# Sample_and_Hold_Main.net
KiCad netlist of a schematic drawn in EAGLE
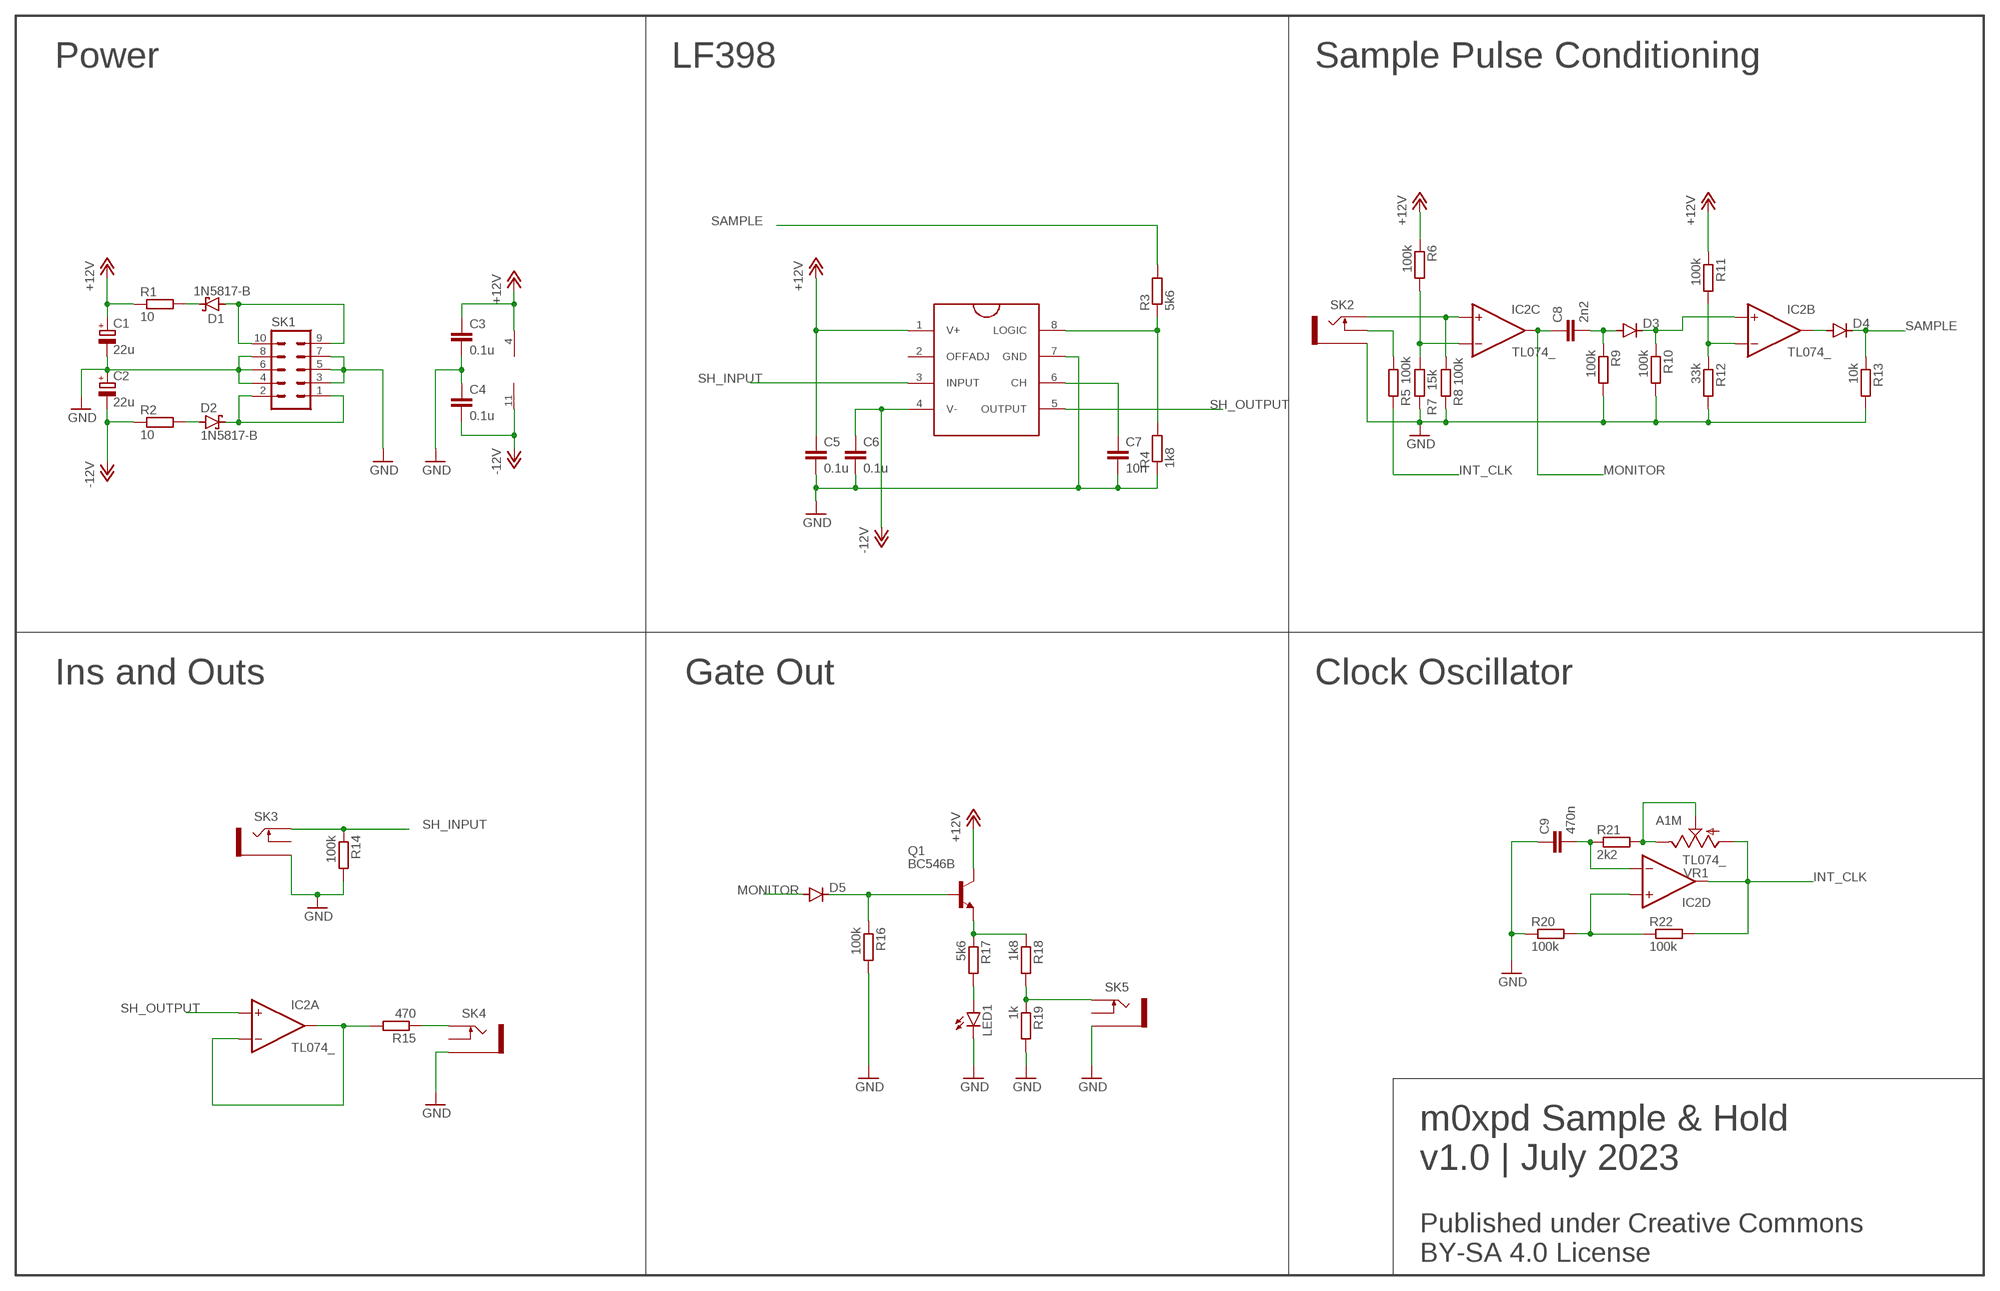
[diagram p0: schematic, sheet 1]

(export (version "E")
  (design (tool "Eeschema 10.0.6"))
  (components
    (comp (ref "C1")
      (value "22u")
      (footprint "eagle-import:E2,5-6")
      (libsource (lib "eagle-import") (part "CPOL-EUE2.5-6"))
    )
    (comp (ref "C2")
      (value "22u")
      (footprint "eagle-import:E2,5-6")
      (libsource (lib "eagle-import") (part "CPOL-EUE2.5-6"))
    )
    (comp (ref "C3")
      (value "0.1u")
      (footprint "eagle-import:C050-024X044")
      (libsource (lib "eagle-import") (part "C-EU050-024X044"))
    )
    (comp (ref "C4")
      (value "0.1u")
      (footprint "eagle-import:C050-024X044")
      (libsource (lib "eagle-import") (part "C-EU050-024X044"))
    )
    (comp (ref "C5")
      (value "0.1u")
      (footprint "eagle-import:C050-024X044")
      (libsource (lib "eagle-import") (part "C-EU050-024X044"))
    )
    (comp (ref "C6")
      (value "0.1u")
      (footprint "eagle-import:C050-024X044")
      (libsource (lib "eagle-import") (part "C-EU050-024X044"))
    )
    (comp (ref "C7")
      (value "10n")
      (footprint "eagle-import:C050-025X075")
      (libsource (lib "eagle-import") (part "C-EU050-025X075"))
    )
    (comp (ref "C8")
      (value "2n2")
      (footprint "eagle-import:C050-024X044")
      (libsource (lib "eagle-import") (part "C-EU050-024X044"))
    )
    (comp (ref "C9")
      (value "470n")
      (footprint "eagle-import:C050-035X075")
      (libsource (lib "eagle-import") (part "C-EU050-035X075"))
    )
    (comp (ref "D1")
      (value "1N5817-B")
      (footprint "eagle-import:DO41-7.6")
      (libsource (lib "eagle-import") (part "1N5817-B"))
    )
    (comp (ref "D2")
      (value "1N5817-B")
      (footprint "eagle-import:DO41-7.6")
      (libsource (lib "eagle-import") (part "1N5817-B"))
    )
    (comp (ref "D3")
      (value "1N4148DO35-7")
      (footprint "eagle-import:DO35-7")
      (libsource (lib "eagle-import") (part "1N4148DO35-7"))
    )
    (comp (ref "D4")
      (value "1N4148DO35-7")
      (footprint "eagle-import:DO35-7")
      (libsource (lib "eagle-import") (part "1N4148DO35-7"))
    )
    (comp (ref "D5")
      (value "1N4148DO35-7")
      (footprint "eagle-import:DO35-7")
      (libsource (lib "eagle-import") (part "1N4148DO35-7"))
    )
    (comp (ref "IC1")
      (value "LF398")
      (footprint "eagle-import:DIL08")
      (libsource (lib "eagle-import") (part "LF398"))
    )
    (comp (ref "IC2")
      (value "TL074_")
      (footprint "eagle-import:DIL14")
      (libsource (lib "eagle-import") (part "TL074_"))
    )
    (comp (ref "LED1")
      (value "LED3MM")
      (footprint "eagle-import:LED3MM")
      (libsource (lib "eagle-import") (part "LED3MM"))
    )
    (comp (ref "Q1")
      (value "BC546B")
      (footprint "eagle-import:TO92-EBC")
      (libsource (lib "eagle-import") (part "BC546B"))
    )
    (comp (ref "R1")
      (value "10")
      (footprint "eagle-import:0204_7")
      (libsource (lib "eagle-import") (part "R-EU_0204/7"))
    )
    (comp (ref "R2")
      (value "10")
      (footprint "eagle-import:0204_7")
      (libsource (lib "eagle-import") (part "R-EU_0204/7"))
    )
    (comp (ref "R3")
      (value "5k6")
      (footprint "eagle-import:0204_7")
      (libsource (lib "eagle-import") (part "R-EU_0204/7"))
    )
    (comp (ref "R4")
      (value "1k8")
      (footprint "eagle-import:0204_7")
      (libsource (lib "eagle-import") (part "R-EU_0204/7"))
    )
    (comp (ref "R5")
      (value "100k")
      (footprint "eagle-import:0204_7")
      (libsource (lib "eagle-import") (part "R-EU_0204/7"))
    )
    (comp (ref "R6")
      (value "100k")
      (footprint "eagle-import:0204_7")
      (libsource (lib "eagle-import") (part "R-EU_0204/7"))
    )
    (comp (ref "R7")
      (value "15k")
      (footprint "eagle-import:0204_7")
      (libsource (lib "eagle-import") (part "R-EU_0204/7"))
    )
    (comp (ref "R8")
      (value "100k")
      (footprint "eagle-import:0204_7")
      (libsource (lib "eagle-import") (part "R-EU_0204/7"))
    )
    (comp (ref "R9")
      (value "100k")
      (footprint "eagle-import:0204_7")
      (libsource (lib "eagle-import") (part "R-EU_0204/7"))
    )
    (comp (ref "R10")
      (value "100k")
      (footprint "eagle-import:0204_7")
      (libsource (lib "eagle-import") (part "R-EU_0204/7"))
    )
    (comp (ref "R11")
      (value "100k")
      (footprint "eagle-import:0204_7")
      (libsource (lib "eagle-import") (part "R-EU_0204/7"))
    )
    (comp (ref "R12")
      (value "33k")
      (footprint "eagle-import:0204_7")
      (libsource (lib "eagle-import") (part "R-EU_0204/7"))
    )
    (comp (ref "R13")
      (value "10k")
      (footprint "eagle-import:0204_7")
      (libsource (lib "eagle-import") (part "R-EU_0204/7"))
    )
    (comp (ref "R14")
      (value "100k")
      (footprint "eagle-import:0204_7")
      (libsource (lib "eagle-import") (part "R-EU_0204/7"))
    )
    (comp (ref "R15")
      (value "470")
      (footprint "eagle-import:0204_7")
      (libsource (lib "eagle-import") (part "R-EU_0204/7"))
    )
    (comp (ref "R16")
      (value "100k")
      (footprint "eagle-import:0204_7")
      (libsource (lib "eagle-import") (part "R-EU_0204/7"))
    )
    (comp (ref "R17")
      (value "5k6")
      (footprint "eagle-import:0204_7")
      (libsource (lib "eagle-import") (part "R-EU_0204/7"))
    )
    (comp (ref "R18")
      (value "1k8")
      (footprint "eagle-import:0204_7")
      (libsource (lib "eagle-import") (part "R-EU_0204/7"))
    )
    (comp (ref "R19")
      (value "1k")
      (footprint "eagle-import:0204_7")
      (libsource (lib "eagle-import") (part "R-EU_0204/7"))
    )
    (comp (ref "R20")
      (value "100k")
      (footprint "eagle-import:0204_7")
      (libsource (lib "eagle-import") (part "R-EU_0204/7"))
    )
    (comp (ref "R21")
      (value "2k2")
      (footprint "eagle-import:0204_7")
      (libsource (lib "eagle-import") (part "R-EU_0204/7"))
    )
    (comp (ref "R22")
      (value "100k")
      (footprint "eagle-import:0204_7")
      (libsource (lib "eagle-import") (part "R-EU_0204/7"))
    )
    (comp (ref "SK1")
      (value "EURO_POWER_HEADERFAT_PADS")
      (footprint "eagle-import:EURO_PWR_HEADER_FAT")
      (libsource (lib "eagle-import") (part "EURO_POWER_HEADERFAT_PADS"))
    )
    (comp (ref "SK2")
      (value "THONKICONNNEW")
      (footprint "eagle-import:WQP-PJ301M-12_JACK")
      (libsource (lib "eagle-import") (part "THONKICONNNEW"))
    )
    (comp (ref "SK3")
      (value "THONKICONNNEW")
      (footprint "eagle-import:WQP-PJ301M-12_JACK")
      (libsource (lib "eagle-import") (part "THONKICONNNEW"))
    )
    (comp (ref "SK4")
      (value "THONKICONNNEW")
      (footprint "eagle-import:WQP-PJ301M-12_JACK")
      (libsource (lib "eagle-import") (part "THONKICONNNEW"))
    )
    (comp (ref "SK5")
      (value "THONKICONNNEW")
      (footprint "eagle-import:WQP-PJ301M-12_JACK")
      (libsource (lib "eagle-import") (part "THONKICONNNEW"))
    )
    (comp (ref "VR1")
      (value "A1M")
      (footprint "eagle-import:9MM_SNAP-IN_POT")
      (libsource (lib "eagle-import") (part "9MM_SNAP-IN_POT_"))
    )
  )
  (nets
    (net (code "1") (name "+12V") (class "Default")
      (node (ref "C1") (pin "+") (pinfunction "+_+") (pintype "passive"))
      (node (ref "C3") (pin "1") (pinfunction "1_1") (pintype "passive"))
      (node (ref "C5") (pin "1") (pinfunction "1_1") (pintype "passive"))
      (node (ref "IC1") (pin "1") (pinfunction "V+_1") (pintype "power_in"))
      (node (ref "IC2") (pin "4") (pinfunction "V+_4") (pintype "power_in"))
      (node (ref "Q1") (pin "C") (pinfunction "C_C") (pintype "passive"))
      (node (ref "R1") (pin "1") (pinfunction "1_1") (pintype "passive"))
      (node (ref "R11") (pin "1") (pinfunction "1_1") (pintype "passive"))
      (node (ref "R6") (pin "1") (pinfunction "1_1") (pintype "passive"))
    )
    (net (code "2") (name "-12V") (class "Default")
      (node (ref "C2") (pin "-") (pinfunction "-_-") (pintype "passive"))
      (node (ref "C4") (pin "2") (pinfunction "2_2") (pintype "passive"))
      (node (ref "C6") (pin "1") (pinfunction "1_1") (pintype "passive"))
      (node (ref "IC1") (pin "4") (pinfunction "V-_4") (pintype "power_in"))
      (node (ref "IC2") (pin "11") (pinfunction "V-_11") (pintype "power_in"))
      (node (ref "R2") (pin "1") (pinfunction "1_1") (pintype "passive"))
    )
    (net (code "3") (name "/INT_CLK") (class "Default")
      (node (ref "IC2") (pin "14") (pinfunction "OUT_14") (pintype "output"))
      (node (ref "R22") (pin "2") (pinfunction "2_2") (pintype "passive"))
      (node (ref "R5") (pin "2") (pinfunction "2_2") (pintype "passive"))
      (node (ref "VR1") (pin "1") (pinfunction "A_1") (pintype "passive"))
    )
    (net (code "4") (name "/MONITOR") (class "Default")
      (node (ref "C8") (pin "1") (pinfunction "1_1") (pintype "passive"))
      (node (ref "D5") (pin "A") (pinfunction "A_A") (pintype "passive"))
      (node (ref "IC2") (pin "8") (pinfunction "OUT_8") (pintype "output"))
    )
    (net (code "5") (name "/SAMPLE") (class "Default")
      (node (ref "D4") (pin "C") (pinfunction "C_C") (pintype "passive"))
      (node (ref "R13") (pin "1") (pinfunction "1_1") (pintype "passive"))
      (node (ref "R3") (pin "2") (pinfunction "2_2") (pintype "passive"))
    )
    (net (code "6") (name "/SH_INPUT") (class "Default")
      (node (ref "IC1") (pin "3") (pinfunction "INPUT_3") (pintype "bidirectional"))
      (node (ref "R14") (pin "1") (pinfunction "1_1") (pintype "passive"))
      (node (ref "SK3") (pin "P$1_TIP") (pinfunction "TIP_P$1_TIP") (pintype "passive"))
    )
    (net (code "7") (name "/SH_OUTPUT") (class "Default")
      (node (ref "IC1") (pin "5") (pinfunction "OUTPUT_5") (pintype "bidirectional"))
      (node (ref "IC2") (pin "3") (pinfunction "+IN_3") (pintype "input"))
    )
    (net (code "8") (name "GND") (class "Default")
      (node (ref "C1") (pin "-") (pinfunction "-_-") (pintype "passive"))
      (node (ref "C2") (pin "+") (pinfunction "+_+") (pintype "passive"))
      (node (ref "C3") (pin "2") (pinfunction "2_2") (pintype "passive"))
      (node (ref "C4") (pin "1") (pinfunction "1_1") (pintype "passive"))
      (node (ref "C5") (pin "2") (pinfunction "2_2") (pintype "passive"))
      (node (ref "C6") (pin "2") (pinfunction "2_2") (pintype "passive"))
      (node (ref "C7") (pin "2") (pinfunction "2_2") (pintype "passive"))
      (node (ref "C9") (pin "1") (pinfunction "1_1") (pintype "passive"))
      (node (ref "IC1") (pin "7") (pinfunction "GND_7") (pintype "power_in"))
      (node (ref "LED1") (pin "K") (pinfunction "C_K") (pintype "passive"))
      (node (ref "R10") (pin "2") (pinfunction "2_2") (pintype "passive"))
      (node (ref "R12") (pin "2") (pinfunction "2_2") (pintype "passive"))
      (node (ref "R13") (pin "2") (pinfunction "2_2") (pintype "passive"))
      (node (ref "R14") (pin "2") (pinfunction "2_2") (pintype "passive"))
      (node (ref "R16") (pin "2") (pinfunction "2_2") (pintype "passive"))
      (node (ref "R19") (pin "2") (pinfunction "2_2") (pintype "passive"))
      (node (ref "R20") (pin "1") (pinfunction "1_1") (pintype "passive"))
      (node (ref "R4") (pin "1") (pinfunction "1_1") (pintype "passive"))
      (node (ref "R7") (pin "2") (pinfunction "2_2") (pintype "passive"))
      (node (ref "R8") (pin "2") (pinfunction "2_2") (pintype "passive"))
      (node (ref "R9") (pin "2") (pinfunction "2_2") (pintype "passive"))
      (node (ref "SK1") (pin "3") (pinfunction "3_3") (pintype "passive"))
      (node (ref "SK1") (pin "4") (pinfunction "4_4") (pintype "passive"))
      (node (ref "SK1") (pin "5") (pinfunction "5_5") (pintype "passive"))
      (node (ref "SK1") (pin "6") (pinfunction "6_6") (pintype "passive"))
      (node (ref "SK1") (pin "7") (pinfunction "7_7") (pintype "passive"))
      (node (ref "SK1") (pin "8") (pinfunction "8_8") (pintype "passive"))
      (node (ref "SK2") (pin "P$3_SLEEVE") (pinfunction "SLEEVE_P$3_SLEEVE") (pintype "passive"))
      (node (ref "SK3") (pin "P$3_SLEEVE") (pinfunction "SLEEVE_P$3_SLEEVE") (pintype "passive"))
      (node (ref "SK4") (pin "P$3_SLEEVE") (pinfunction "SLEEVE_P$3_SLEEVE") (pintype "passive"))
      (node (ref "SK5") (pin "P$3_SLEEVE") (pinfunction "SLEEVE_P$3_SLEEVE") (pintype "passive"))
    )
    (net (code "9") (name "Net-(C8-Pad2)") (class "Default")
      (node (ref "C8") (pin "2") (pinfunction "2_2") (pintype "passive"))
      (node (ref "D3") (pin "A") (pinfunction "A_A") (pintype "passive"))
      (node (ref "R9") (pin "1") (pinfunction "1_1") (pintype "passive"))
    )
    (net (code "10") (name "Net-(D1-PadA)") (class "Default")
      (node (ref "D1") (pin "A") (pinfunction "A_A") (pintype "passive"))
      (node (ref "SK1") (pin "10") (pinfunction "10_10") (pintype "passive"))
      (node (ref "SK1") (pin "9") (pinfunction "9_9") (pintype "passive"))
    )
    (net (code "11") (name "Net-(D1-PadC)") (class "Default")
      (node (ref "D1") (pin "C") (pinfunction "C_C") (pintype "passive"))
      (node (ref "R1") (pin "2") (pinfunction "2_2") (pintype "passive"))
    )
    (net (code "12") (name "Net-(D2-PadA)") (class "Default")
      (node (ref "D2") (pin "A") (pinfunction "A_A") (pintype "passive"))
      (node (ref "R2") (pin "2") (pinfunction "2_2") (pintype "passive"))
    )
    (net (code "13") (name "Net-(D2-PadC)") (class "Default")
      (node (ref "D2") (pin "C") (pinfunction "C_C") (pintype "passive"))
      (node (ref "SK1") (pin "1") (pinfunction "1_1") (pintype "passive"))
      (node (ref "SK1") (pin "2") (pinfunction "2_2") (pintype "passive"))
    )
    (net (code "14") (name "Net-(D5-PadC)") (class "Default")
      (node (ref "D5") (pin "C") (pinfunction "C_C") (pintype "passive"))
      (node (ref "Q1") (pin "B") (pinfunction "B_B") (pintype "passive"))
      (node (ref "R16") (pin "1") (pinfunction "1_1") (pintype "passive"))
    )
    (net (code "15") (name "Net-(IC1-CH)") (class "Default")
      (node (ref "C7") (pin "1") (pinfunction "1_1") (pintype "passive"))
      (node (ref "IC1") (pin "6") (pinfunction "CH_6") (pintype "bidirectional"))
    )
    (net (code "16") (name "Net-(IC1-LOGIC)") (class "Default")
      (node (ref "IC1") (pin "8") (pinfunction "LOGIC_8") (pintype "bidirectional"))
      (node (ref "R3") (pin "1") (pinfunction "1_1") (pintype "passive"))
      (node (ref "R4") (pin "2") (pinfunction "2_2") (pintype "passive"))
    )
    (net (code "17") (name "Net-(IC2A--IN)") (class "Default")
      (node (ref "IC2") (pin "1") (pinfunction "OUT_1") (pintype "output"))
      (node (ref "IC2") (pin "2") (pinfunction "-IN_2") (pintype "input"))
      (node (ref "R15") (pin "2") (pinfunction "2_2") (pintype "passive"))
    )
    (net (code "18") (name "Net-(IC2B-+IN)") (class "Default")
      (node (ref "D3") (pin "C") (pinfunction "C_C") (pintype "passive"))
      (node (ref "IC2") (pin "5") (pinfunction "+IN_5") (pintype "input"))
      (node (ref "R10") (pin "1") (pinfunction "1_1") (pintype "passive"))
    )
    (net (code "19") (name "Net-(IC2B--IN)") (class "Default")
      (node (ref "IC2") (pin "6") (pinfunction "-IN_6") (pintype "input"))
      (node (ref "R11") (pin "2") (pinfunction "2_2") (pintype "passive"))
      (node (ref "R12") (pin "1") (pinfunction "1_1") (pintype "passive"))
    )
    (net (code "20") (name "Net-(IC2B-OUT)") (class "Default")
      (node (ref "D4") (pin "A") (pinfunction "A_A") (pintype "passive"))
      (node (ref "IC2") (pin "7") (pinfunction "OUT_7") (pintype "output"))
    )
    (net (code "21") (name "Net-(IC2C-+IN)") (class "Default")
      (node (ref "IC2") (pin "10") (pinfunction "+IN_10") (pintype "input"))
      (node (ref "R8") (pin "1") (pinfunction "1_1") (pintype "passive"))
      (node (ref "SK2") (pin "P$1_TIP") (pinfunction "TIP_P$1_TIP") (pintype "passive"))
    )
    (net (code "22") (name "Net-(IC2C--IN)") (class "Default")
      (node (ref "IC2") (pin "9") (pinfunction "-IN_9") (pintype "input"))
      (node (ref "R6") (pin "2") (pinfunction "2_2") (pintype "passive"))
      (node (ref "R7") (pin "1") (pinfunction "1_1") (pintype "passive"))
    )
    (net (code "23") (name "Net-(IC2D-+IN)") (class "Default")
      (node (ref "IC2") (pin "12") (pinfunction "+IN_12") (pintype "input"))
      (node (ref "R20") (pin "2") (pinfunction "2_2") (pintype "passive"))
      (node (ref "R22") (pin "1") (pinfunction "1_1") (pintype "passive"))
    )
    (net (code "24") (name "Net-(IC2D--IN)") (class "Default")
      (node (ref "C9") (pin "2") (pinfunction "2_2") (pintype "passive"))
      (node (ref "IC2") (pin "13") (pinfunction "-IN_13") (pintype "input"))
      (node (ref "R21") (pin "1") (pinfunction "1_1") (pintype "passive"))
    )
    (net (code "25") (name "Net-(LED1-PadA)") (class "Default")
      (node (ref "LED1") (pin "A") (pinfunction "A_A") (pintype "passive"))
      (node (ref "R17") (pin "2") (pinfunction "2_2") (pintype "passive"))
    )
    (net (code "26") (name "Net-(Q1-PadE)") (class "Default")
      (node (ref "Q1") (pin "E") (pinfunction "E_E") (pintype "passive"))
      (node (ref "R17") (pin "1") (pinfunction "1_1") (pintype "passive"))
      (node (ref "R18") (pin "1") (pinfunction "1_1") (pintype "passive"))
    )
    (net (code "27") (name "Net-(SK2-SWITCH)") (class "Default")
      (node (ref "R5") (pin "1") (pinfunction "1_1") (pintype "passive"))
      (node (ref "SK2") (pin "P$2_SWITCH") (pinfunction "SWITCH_P$2_SWITCH") (pintype "passive"))
    )
    (net (code "28") (name "Net-(SK4-TIP)") (class "Default")
      (node (ref "R15") (pin "1") (pinfunction "1_1") (pintype "passive"))
      (node (ref "SK4") (pin "P$1_TIP") (pinfunction "TIP_P$1_TIP") (pintype "passive"))
    )
    (net (code "29") (name "Net-(SK5-TIP)") (class "Default")
      (node (ref "R18") (pin "2") (pinfunction "2_2") (pintype "passive"))
      (node (ref "R19") (pin "1") (pinfunction "1_1") (pintype "passive"))
      (node (ref "SK5") (pin "P$1_TIP") (pinfunction "TIP_P$1_TIP") (pintype "passive"))
    )
    (net (code "30") (name "Net-(VR1-E)") (class "Default")
      (node (ref "R21") (pin "2") (pinfunction "2_2") (pintype "passive"))
      (node (ref "VR1") (pin "2") (pinfunction "S_2") (pintype "passive"))
      (node (ref "VR1") (pin "3") (pinfunction "E_3") (pintype "passive"))
    )
    (net (code "31") (name "unconnected-(IC1-OFFADJ-Pad2)") (class "Default")
      (node (ref "IC1") (pin "2") (pinfunction "OFFADJ_2") (pintype "bidirectional"))
    )
    (net (code "32") (name "unconnected-(SK3-SWITCH-PadP$2_SWITCH)") (class "Default")
      (node (ref "SK3") (pin "P$2_SWITCH") (pinfunction "SWITCH_P$2_SWITCH") (pintype "passive"))
    )
    (net (code "33") (name "unconnected-(SK4-SWITCH-PadP$2_SWITCH)") (class "Default")
      (node (ref "SK4") (pin "P$2_SWITCH") (pinfunction "SWITCH_P$2_SWITCH") (pintype "passive"))
    )
    (net (code "34") (name "unconnected-(SK5-SWITCH-PadP$2_SWITCH)") (class "Default")
      (node (ref "SK5") (pin "P$2_SWITCH") (pinfunction "SWITCH_P$2_SWITCH") (pintype "passive"))
    )
  )
)
